# Main_Motor_Connector.net
KiCad netlist of a schematic drawn in Altium Designer
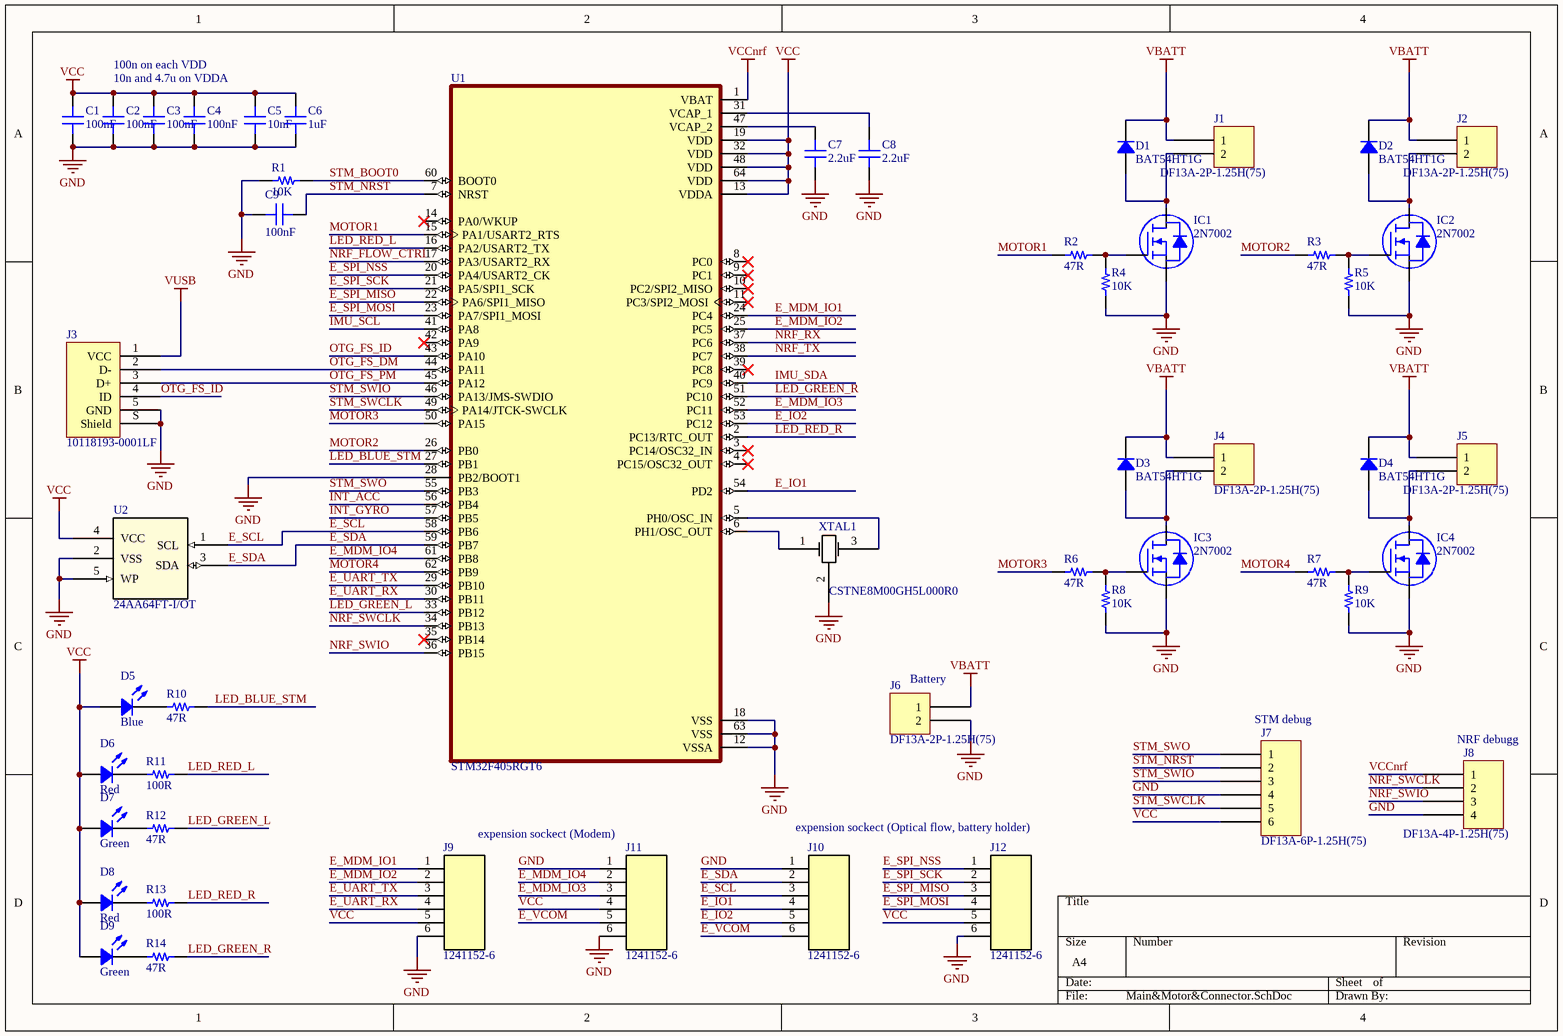
[diagram p0: Main&Motor&Connector.SchDoc]

(export (version "E")
  (design (tool "Eeschema 10.0.6"))
  (components
    (comp (ref "C1")
      (value "100nF")
      (footprint "CAP 0402_1005")
      (description "CAP CER 0.1UF 16V Y5V 0402")
      (fields (field (name "PART NUMBER") "C0402C104M4VACTU") (field (name "MANUFACTURER") "KEMET"))
      (libsource (lib "Celestial Altium Library - altium_library") (part "Capacitor"))
    )
    (comp (ref "C2")
      (value "100nF")
      (footprint "CAP 0402_1005")
      (description "CAP CER 0.1UF 16V Y5V 0402")
      (fields (field (name "PART NUMBER") "C0402C104M4VACTU") (field (name "MANUFACTURER") "KEMET"))
      (libsource (lib "Celestial Altium Library - altium_library") (part "Capacitor"))
    )
    (comp (ref "C3")
      (value "100nF")
      (footprint "CAP 0402_1005")
      (description "CAP CER 0.1UF 16V Y5V 0402")
      (fields (field (name "PART NUMBER") "C0402C104M4VACTU") (field (name "MANUFACTURER") "KEMET"))
      (libsource (lib "Celestial Altium Library - altium_library") (part "Capacitor"))
    )
    (comp (ref "C4")
      (value "100nF")
      (footprint "CAP 0402_1005")
      (description "CAP CER 0.1UF 16V Y5V 0402")
      (fields (field (name "PART NUMBER") "C0402C104M4VACTU") (field (name "MANUFACTURER") "KEMET"))
      (libsource (lib "Celestial Altium Library - altium_library") (part "Capacitor"))
    )
    (comp (ref "C5")
      (value "10nF")
      (footprint "CAP 0402_1005")
      (description "CAP CER 0.1UF 16V Y5V 0402")
      (fields (field (name "PART NUMBER") "C0402C104M4VACTU") (field (name "MANUFACTURER") "KEMET"))
      (libsource (lib "Celestial Altium Library - altium_library") (part "Capacitor"))
    )
    (comp (ref "C6")
      (value "1uF")
      (footprint "CAP 0402_1005")
      (description "CAP CER 0.1UF 16V Y5V 0402")
      (fields (field (name "PART NUMBER") "C0402C104M4VACTU") (field (name "MANUFACTURER") "KEMET"))
      (libsource (lib "Celestial Altium Library - altium_library") (part "Capacitor"))
    )
    (comp (ref "C7")
      (value "2.2uF")
      (footprint "CAP 0603_1608")
      (description "CAP CER 100PF 50V C0G/NP0 0603")
      (fields (field (name "PART NUMBER") "C0603X101F5GAC7867") (field (name "MANUFACTURER") "KEMET"))
      (libsource (lib "Celestial Altium Library - altium_library") (part "Capacitor"))
    )
    (comp (ref "C8")
      (value "2.2uF")
      (footprint "CAP 0603_1608")
      (description "CAP CER 100PF 50V C0G/NP0 0603")
      (fields (field (name "PART NUMBER") "C0603X101F5GAC7867") (field (name "MANUFACTURER") "KEMET"))
      (libsource (lib "Celestial Altium Library - altium_library") (part "Capacitor"))
    )
    (comp (ref "C9")
      (value "100nF")
      (footprint "CAP 0402_1005")
      (description "CAP CER 0.1UF 16V Y5V 0402")
      (fields (field (name "PART NUMBER") "C0402C104M4VACTU") (field (name "MANUFACTURER") "KEMET"))
      (libsource (lib "Celestial Altium Library - altium_library") (part "Capacitor"))
    )
    (comp (ref "D1")
      (value "BAT54HT1G")
      (footprint "SOD323")
      (description "DIODE SCHOTTKY 30V 200MA SOD323")
      (fields (field (name "MANUFACTURER") "ON Semiconductor"))
      (libsource (lib "Celestial Altium Library - altium_library") (part "Diode"))
    )
    (comp (ref "D2")
      (value "BAT54HT1G")
      (footprint "SOD323")
      (description "DIODE SCHOTTKY 30V 200MA SOD323")
      (fields (field (name "MANUFACTURER") "ON Semiconductor"))
      (libsource (lib "Celestial Altium Library - altium_library") (part "Diode"))
    )
    (comp (ref "D3")
      (value "BAT54HT1G")
      (footprint "SOD323")
      (description "DIODE SCHOTTKY 30V 200MA SOD323")
      (fields (field (name "MANUFACTURER") "ON Semiconductor"))
      (libsource (lib "Celestial Altium Library - altium_library") (part "Diode"))
    )
    (comp (ref "D4")
      (value "BAT54HT1G")
      (footprint "SOD323")
      (description "DIODE SCHOTTKY 30V 200MA SOD323")
      (fields (field (name "MANUFACTURER") "ON Semiconductor"))
      (libsource (lib "Celestial Altium Library - altium_library") (part "Diode"))
    )
    (comp (ref "D5")
      (value "Blue")
      (footprint "LED 0603_1608 BLUE")
      (description "LED BLUE CLEAR 2SMD")
      (fields (field (name "PART NUMBER") "XZFBB53W-1") (field (name "MANUFACTURER") "SunLED"))
      (libsource (lib "Celestial Altium Library - altium_library") (part "LED"))
    )
    (comp (ref "D6")
      (value "Red")
      (footprint "LED 0603_1608 RED")
      (description "LED RED 0603 SMD")
      (fields (field (name "PART NUMBER") "5973005507F") (field (name "MANUFACTURER") "Dialight"))
      (libsource (lib "Celestial Altium Library - altium_library") (part "LED"))
    )
    (comp (ref "D7")
      (value "Green")
      (footprint "LED 0603_1608 GREEN")
      (description "LED GREEN CLEAR CHIP SMD")
      (fields (field (name "PART NUMBER") "XZVG53W-3") (field (name "MANUFACTURER") "SunLED"))
      (libsource (lib "Celestial Altium Library - altium_library") (part "LED"))
    )
    (comp (ref "D8")
      (value "Red")
      (footprint "LED 0603_1608 RED")
      (description "LED RED 0603 SMD")
      (fields (field (name "PART NUMBER") "5973005507F") (field (name "MANUFACTURER") "Dialight"))
      (libsource (lib "Celestial Altium Library - altium_library") (part "LED"))
    )
    (comp (ref "D9")
      (value "Green")
      (footprint "LED 0603_1608 GREEN")
      (description "LED GREEN CLEAR CHIP SMD")
      (fields (field (name "PART NUMBER") "XZVG53W-3") (field (name "MANUFACTURER") "SunLED"))
      (libsource (lib "Celestial Altium Library - altium_library") (part "LED"))
    )
    (comp (ref "IC1")
      (value "2N7002")
      (footprint "ON SEMI SOT-23-3")
      (description "MOSFET N-CH 60V 115MA SOT-23")
      (fields (field (name "MANUFACTURER") "ON Semiconductor"))
      (libsource (lib "Celestial Altium Library - altium_library") (part "ON SEMI MOSFET N-CH SOT-23-3"))
    )
    (comp (ref "IC2")
      (value "2N7002")
      (footprint "ON SEMI SOT-23-3")
      (description "MOSFET N-CH 60V 115MA SOT-23")
      (fields (field (name "MANUFACTURER") "ON Semiconductor"))
      (libsource (lib "Celestial Altium Library - altium_library") (part "ON SEMI MOSFET N-CH SOT-23-3"))
    )
    (comp (ref "IC3")
      (value "2N7002")
      (footprint "ON SEMI SOT-23-3")
      (description "MOSFET N-CH 60V 115MA SOT-23")
      (fields (field (name "MANUFACTURER") "ON Semiconductor"))
      (libsource (lib "Celestial Altium Library - altium_library") (part "ON SEMI MOSFET N-CH SOT-23-3"))
    )
    (comp (ref "IC4")
      (value "2N7002")
      (footprint "ON SEMI SOT-23-3")
      (description "MOSFET N-CH 60V 115MA SOT-23")
      (fields (field (name "MANUFACTURER") "ON Semiconductor"))
      (libsource (lib "Celestial Altium Library - altium_library") (part "ON SEMI MOSFET N-CH SOT-23-3"))
    )
    (comp (ref "J1")
      (value "DF13A-2P-1.25H(75)")
      (footprint "HIROSE DF13A-2P-1.25H")
      (description "CONN HEADER SMD R/A 2POS 1.25MM")
      (fields (field (name "MANUFACTURER") "Hirose Electric Co Ltd"))
      (libsource (lib "Celestial Altium Library - altium_library") (part "2 Pin"))
    )
    (comp (ref "J2")
      (value "DF13A-2P-1.25H(75)")
      (footprint "HIROSE DF13A-2P-1.25H")
      (description "CONN HEADER SMD R/A 2POS 1.25MM")
      (fields (field (name "MANUFACTURER") "Hirose Electric Co Ltd"))
      (libsource (lib "Celestial Altium Library - altium_library") (part "2 Pin"))
    )
    (comp (ref "J3")
      (value "10118193-0001LF")
      (footprint "FCI USB 10118193-0001LF")
      (description "CONN RCPT USB2.0 MICRO B SMD R/A")
      (fields (field (name "MANUFACTURER") "Amphenol ICC (FCI)"))
      (libsource (lib "Celestial Altium Library - altium_library") (part "USB 2.0 Type B Micro"))
    )
    (comp (ref "J4")
      (value "DF13A-2P-1.25H(75)")
      (footprint "HIROSE DF13A-2P-1.25H")
      (description "CONN HEADER SMD R/A 2POS 1.25MM")
      (fields (field (name "MANUFACTURER") "Hirose Electric Co Ltd"))
      (libsource (lib "Celestial Altium Library - altium_library") (part "2 Pin"))
    )
    (comp (ref "J5")
      (value "DF13A-2P-1.25H(75)")
      (footprint "HIROSE DF13A-2P-1.25H")
      (description "CONN HEADER SMD R/A 2POS 1.25MM")
      (fields (field (name "MANUFACTURER") "Hirose Electric Co Ltd"))
      (libsource (lib "Celestial Altium Library - altium_library") (part "2 Pin"))
    )
    (comp (ref "J6")
      (value "DF13A-2P-1.25H(75)")
      (footprint "HIROSE DF13A-2P-1.25H")
      (description "CONN HEADER SMD R/A 2POS 1.25MM")
      (fields (field (name "MANUFACTURER") "Hirose Electric Co Ltd"))
      (libsource (lib "") (part "2 Pin_1"))
    )
    (comp (ref "J7")
      (value "DF13A-6P-1.25H(75)")
      (footprint "HIROSE DF13A-6P-1.25H")
      (description "CONN HEADER SMD R/A 6POS 1.25MM")
      (fields (field (name "MANUFACTURER") "Hirose Electric Co Ltd"))
      (libsource (lib "Celestial Altium Library - altium_library") (part "6 Pin"))
    )
    (comp (ref "J8")
      (value "DF13A-4P-1.25H(75)")
      (footprint "HIROSE DF13A-4P-1.25H")
      (description "CONN HEADER SMD R/A 4POS 1.25MM")
      (fields (field (name "MANUFACTURER") "Hirose Electric Co Ltd"))
      (libsource (lib "Celestial Altium Library - altium_library") (part "4 Pin"))
    )
    (comp (ref "J9")
      (value "1241152-6")
      (footprint "CONN_1241152-6_T")
      (description "con 6pos 2.54mm TE connectivity")
      (fields (field (name "COPYRIGHT") "Copyright (C) 2016 Accelerated Designs. All rights reserved"))
      (libsource (lib "Schlib1") (part "1241152-6"))
    )
    (comp (ref "J10")
      (value "1241152-6")
      (footprint "CONN_1241152-6_T")
      (description "con 6pos 2.54mm TE connectivity")
      (fields (field (name "COPYRIGHT") "Copyright (C) 2016 Accelerated Designs. All rights reserved"))
      (libsource (lib "Schlib1") (part "1241152-6"))
    )
    (comp (ref "J11")
      (value "1241152-6")
      (footprint "CONN_1241152-6_T")
      (description "con 6pos 2.54mm TE connectivity")
      (fields (field (name "COPYRIGHT") "Copyright (C) 2016 Accelerated Designs. All rights reserved"))
      (libsource (lib "Schlib1") (part "1241152-6"))
    )
    (comp (ref "J12")
      (value "1241152-6")
      (footprint "CONN_1241152-6_T")
      (description "con 6pos 2.54mm TE connectivity")
      (fields (field (name "COPYRIGHT") "Copyright (C) 2016 Accelerated Designs. All rights reserved"))
      (libsource (lib "Schlib1") (part "1241152-6"))
    )
    (comp (ref "R1")
      (value "10K")
      (footprint "RES 0402_1005")
      (description "RES SMD 4.7K OHM 1% 1/16W 0402")
      (fields (field (name "PART NUMBER") "RT0402FRE074K7L") (field (name "MANUFACTURER") "Yageo"))
      (libsource (lib "Celestial Altium Library - altium_library") (part "Resistor"))
    )
    (comp (ref "R2")
      (value "47R")
      (footprint "RES 0603_1608")
      (description "RES SMD 10K OHM 1% 1/10W 0603")
      (fields (field (name "PART NUMBER") "AC0603FR-0710KL") (field (name "MANUFACTURER") "Yageo"))
      (libsource (lib "Celestial Altium Library - altium_library") (part "Resistor"))
    )
    (comp (ref "R3")
      (value "47R")
      (footprint "RES 0603_1608")
      (description "RES SMD 10K OHM 1% 1/10W 0603")
      (fields (field (name "PART NUMBER") "AC0603FR-0710KL") (field (name "MANUFACTURER") "Yageo"))
      (libsource (lib "Celestial Altium Library - altium_library") (part "Resistor"))
    )
    (comp (ref "R4")
      (value "10K")
      (footprint "RES 0603_1608")
      (description "RES SMD 10K OHM 1% 1/10W 0603")
      (fields (field (name "PART NUMBER") "AC0603FR-0710KL") (field (name "MANUFACTURER") "Yageo"))
      (libsource (lib "Celestial Altium Library - altium_library") (part "Resistor"))
    )
    (comp (ref "R5")
      (value "10K")
      (footprint "RES 0603_1608")
      (description "RES SMD 10K OHM 1% 1/10W 0603")
      (fields (field (name "PART NUMBER") "AC0603FR-0710KL") (field (name "MANUFACTURER") "Yageo"))
      (libsource (lib "Celestial Altium Library - altium_library") (part "Resistor"))
    )
    (comp (ref "R6")
      (value "47R")
      (footprint "RES 0603_1608")
      (description "RES SMD 10K OHM 1% 1/10W 0603")
      (fields (field (name "PART NUMBER") "AC0603FR-0710KL") (field (name "MANUFACTURER") "Yageo"))
      (libsource (lib "Celestial Altium Library - altium_library") (part "Resistor"))
    )
    (comp (ref "R7")
      (value "47R")
      (footprint "RES 0603_1608")
      (description "RES SMD 10K OHM 1% 1/10W 0603")
      (fields (field (name "PART NUMBER") "AC0603FR-0710KL") (field (name "MANUFACTURER") "Yageo"))
      (libsource (lib "Celestial Altium Library - altium_library") (part "Resistor"))
    )
    (comp (ref "R8")
      (value "10K")
      (footprint "RES 0603_1608")
      (description "RES SMD 10K OHM 1% 1/10W 0603")
      (fields (field (name "PART NUMBER") "AC0603FR-0710KL") (field (name "MANUFACTURER") "Yageo"))
      (libsource (lib "Celestial Altium Library - altium_library") (part "Resistor"))
    )
    (comp (ref "R9")
      (value "10K")
      (footprint "RES 0603_1608")
      (description "RES SMD 10K OHM 1% 1/10W 0603")
      (fields (field (name "PART NUMBER") "AC0603FR-0710KL") (field (name "MANUFACTURER") "Yageo"))
      (libsource (lib "Celestial Altium Library - altium_library") (part "Resistor"))
    )
    (comp (ref "R10")
      (value "47R")
      (footprint "RES 0603_1608")
      (description "RES SMD 10K OHM 1% 1/10W 0603")
      (fields (field (name "PART NUMBER") "AC0603FR-0710KL") (field (name "MANUFACTURER") "Yageo"))
      (libsource (lib "Celestial Altium Library - altium_library") (part "Resistor"))
    )
    (comp (ref "R11")
      (value "100R")
      (footprint "RES 0603_1608")
      (description "RES SMD 10K OHM 1% 1/10W 0603")
      (fields (field (name "PART NUMBER") "AC0603FR-0710KL") (field (name "MANUFACTURER") "Yageo"))
      (libsource (lib "Celestial Altium Library - altium_library") (part "Resistor"))
    )
    (comp (ref "R12")
      (value "47R")
      (footprint "RES 0603_1608")
      (description "RES SMD 10K OHM 1% 1/10W 0603")
      (fields (field (name "PART NUMBER") "AC0603FR-0710KL") (field (name "MANUFACTURER") "Yageo"))
      (libsource (lib "Celestial Altium Library - altium_library") (part "Resistor"))
    )
    (comp (ref "R13")
      (value "100R")
      (footprint "RES 0603_1608")
      (description "RES SMD 10K OHM 1% 1/10W 0603")
      (fields (field (name "PART NUMBER") "AC0603FR-0710KL") (field (name "MANUFACTURER") "Yageo"))
      (libsource (lib "Celestial Altium Library - altium_library") (part "Resistor"))
    )
    (comp (ref "R14")
      (value "47R")
      (footprint "RES 0603_1608")
      (description "RES SMD 10K OHM 1% 1/10W 0603")
      (fields (field (name "PART NUMBER") "AC0603FR-0710KL") (field (name "MANUFACTURER") "Yageo"))
      (libsource (lib "Celestial Altium Library - altium_library") (part "Resistor"))
    )
    (comp (ref "U1")
      (value "STM32F405RGT6")
      (footprint "QFP50P1200X1200X160-64N")
      (description "ARMÂ® CortexÂ®-M4 STM32F4 Microcontroller IC 32-Bit 168MHz 1MB _1M x 8_ FLASH 64-LQFP _10x10_")
      (fields (field (name "MF") "STMicroelectronics") (field (name "DIGI-KEY_PART_NUMBER") "497-11767-ND"))
      (libsource (lib "altium-import") (part "root_0_STM32F405RGT6_"))
    )
    (comp (ref "U2")
      (value "24AA64FT-I/OT")
      (footprint "SOT-23-5_MC_MCH")
      (description "No Description Available")
      (fields (field (name "COPYRIGHT") "Copyright (C) 2018 Accelerated Designs. All rights reserved"))
      (libsource (lib "Schlib1") (part "24AA64FT-I/OT"))
    )
    (comp (ref "XTAL1")
      (value "CSTNE8M00GH5L000R0")
      (footprint "CSTNE8M00GH5L000")
      (description "No Description Available")
      (fields (field (name "COPYRIGHT") "Copyright (C) 2018 Accelerated Designs. All rights reserved"))
      (libsource (lib "Schlib1") (part "CSTNE8M00GH5L000"))
    )
  )
  (nets
    (net (code "1") (name "/E_IO1") (class "Default")
      (node (ref "J10") (pin "4") (pinfunction "4_4") (pintype "passive"))
      (node (ref "U1") (pin "54") (pinfunction "PD2_54") (pintype "bidirectional"))
    )
    (net (code "2") (name "/E_IO2") (class "Default")
      (node (ref "J10") (pin "5") (pinfunction "5_5") (pintype "passive"))
      (node (ref "U1") (pin "53") (pinfunction "PC12_53") (pintype "bidirectional"))
    )
    (net (code "3") (name "/E_MDM_IO1") (class "Default")
      (node (ref "J9") (pin "1") (pinfunction "1_1") (pintype "passive"))
      (node (ref "U1") (pin "24") (pinfunction "PC4_24") (pintype "bidirectional"))
    )
    (net (code "4") (name "/E_MDM_IO2") (class "Default")
      (node (ref "J9") (pin "2") (pinfunction "2_2") (pintype "passive"))
      (node (ref "U1") (pin "25") (pinfunction "PC5_25") (pintype "bidirectional"))
    )
    (net (code "5") (name "/E_MDM_IO3") (class "Default")
      (node (ref "J11") (pin "3") (pinfunction "3_3") (pintype "passive"))
      (node (ref "U1") (pin "52") (pinfunction "PC11_52") (pintype "bidirectional"))
    )
    (net (code "6") (name "/E_MDM_IO4") (class "Default")
      (node (ref "J11") (pin "2") (pinfunction "2_2") (pintype "passive"))
      (node (ref "U1") (pin "61") (pinfunction "PB8_61") (pintype "bidirectional"))
    )
    (net (code "7") (name "/E_SCL") (class "Default")
      (node (ref "J10") (pin "3") (pinfunction "3_3") (pintype "passive"))
      (node (ref "U1") (pin "58") (pinfunction "PB6_58") (pintype "bidirectional"))
      (node (ref "U2") (pin "1") (pinfunction "SCL_1") (pintype "input"))
    )
    (net (code "8") (name "/E_SDA") (class "Default")
      (node (ref "J10") (pin "2") (pinfunction "2_2") (pintype "passive"))
      (node (ref "U1") (pin "59") (pinfunction "PB7_59") (pintype "bidirectional"))
      (node (ref "U2") (pin "3") (pinfunction "SDA_3") (pintype "bidirectional"))
    )
    (net (code "9") (name "/E_SPI_MISO") (class "Default")
      (node (ref "J12") (pin "3") (pinfunction "3_3") (pintype "passive"))
      (node (ref "U1") (pin "22") (pinfunction "PA6/SPI1_MISO_22") (pintype "bidirectional"))
    )
    (net (code "10") (name "/E_SPI_MOSI") (class "Default")
      (node (ref "J12") (pin "4") (pinfunction "4_4") (pintype "passive"))
      (node (ref "U1") (pin "23") (pinfunction "PA7/SPI1_MOSI_23") (pintype "bidirectional"))
    )
    (net (code "11") (name "/E_SPI_NSS") (class "Default")
      (node (ref "J12") (pin "1") (pinfunction "1_1") (pintype "passive"))
      (node (ref "U1") (pin "20") (pinfunction "PA4/USART2_CK_20") (pintype "bidirectional"))
    )
    (net (code "12") (name "/E_SPI_SCK") (class "Default")
      (node (ref "J12") (pin "2") (pinfunction "2_2") (pintype "passive"))
      (node (ref "U1") (pin "21") (pinfunction "PA5/SPI1_SCK_21") (pintype "bidirectional"))
    )
    (net (code "13") (name "/E_UART_RX") (class "Default")
      (node (ref "J9") (pin "4") (pinfunction "4_4") (pintype "passive"))
      (node (ref "U1") (pin "30") (pinfunction "PB11_30") (pintype "bidirectional"))
    )
    (net (code "14") (name "/E_UART_TX") (class "Default")
      (node (ref "J9") (pin "3") (pinfunction "3_3") (pintype "passive"))
      (node (ref "U1") (pin "29") (pinfunction "PB10_29") (pintype "bidirectional"))
    )
    (net (code "15") (name "/E_VCOM") (class "Default")
      (node (ref "J10") (pin "6") (pinfunction "6_6") (pintype "passive"))
      (node (ref "J11") (pin "5") (pinfunction "5_5") (pintype "passive"))
    )
    (net (code "16") (name "/IMU_SCL") (class "Default")
      (node (ref "U1") (pin "41") (pinfunction "PA8_41") (pintype "bidirectional"))
    )
    (net (code "17") (name "/IMU_SDA") (class "Default")
      (node (ref "U1") (pin "40") (pinfunction "PC9_40") (pintype "bidirectional"))
    )
    (net (code "18") (name "/INT_ACC") (class "Default")
      (node (ref "U1") (pin "56") (pinfunction "PB4_56") (pintype "bidirectional"))
    )
    (net (code "19") (name "/INT_GYRO") (class "Default")
      (node (ref "U1") (pin "57") (pinfunction "PB5_57") (pintype "bidirectional"))
    )
    (net (code "20") (name "/LED_BLUE_STM") (class "Default")
      (node (ref "R10") (pin "1") (pinfunction "1_1") (pintype "passive"))
      (node (ref "U1") (pin "27") (pinfunction "PB1_27") (pintype "bidirectional"))
    )
    (net (code "21") (name "/LED_GREEN_L") (class "Default")
      (node (ref "R12") (pin "1") (pinfunction "1_1") (pintype "passive"))
      (node (ref "U1") (pin "33") (pinfunction "PB12_33") (pintype "bidirectional"))
    )
    (net (code "22") (name "/LED_GREEN_R") (class "Default")
      (node (ref "R14") (pin "1") (pinfunction "1_1") (pintype "passive"))
      (node (ref "U1") (pin "51") (pinfunction "PC10_51") (pintype "bidirectional"))
    )
    (net (code "23") (name "/LED_RED_L") (class "Default")
      (node (ref "R11") (pin "1") (pinfunction "1_1") (pintype "passive"))
      (node (ref "U1") (pin "16") (pinfunction "PA2/USART2_TX_16") (pintype "bidirectional"))
    )
    (net (code "24") (name "/LED_RED_R") (class "Default")
      (node (ref "R13") (pin "1") (pinfunction "1_1") (pintype "passive"))
      (node (ref "U1") (pin "2") (pinfunction "PC13/RTC_OUT_2") (pintype "bidirectional"))
    )
    (net (code "25") (name "/MOTOR1") (class "Default")
      (node (ref "R2") (pin "1") (pinfunction "1_1") (pintype "passive"))
      (node (ref "U1") (pin "15") (pinfunction "PA1/USART2_RTS_15") (pintype "bidirectional"))
    )
    (net (code "26") (name "/MOTOR2") (class "Default")
      (node (ref "R3") (pin "1") (pinfunction "1_1") (pintype "passive"))
      (node (ref "U1") (pin "26") (pinfunction "PB0_26") (pintype "bidirectional"))
    )
    (net (code "27") (name "/MOTOR3") (class "Default")
      (node (ref "R6") (pin "1") (pinfunction "1_1") (pintype "passive"))
      (node (ref "U1") (pin "50") (pinfunction "PA15_50") (pintype "bidirectional"))
    )
    (net (code "28") (name "/MOTOR4") (class "Default")
      (node (ref "R7") (pin "1") (pinfunction "1_1") (pintype "passive"))
      (node (ref "U1") (pin "62") (pinfunction "PB9_62") (pintype "bidirectional"))
    )
    (net (code "29") (name "/NRF_FLOW_CTRL") (class "Default")
      (node (ref "U1") (pin "17") (pinfunction "PA3/USART2_RX_17") (pintype "bidirectional"))
    )
    (net (code "30") (name "/NRF_RX") (class "Default")
      (node (ref "U1") (pin "37") (pinfunction "PC6_37") (pintype "bidirectional"))
    )
    (net (code "31") (name "/NRF_SWCLK") (class "Default")
      (node (ref "J8") (pin "2") (pinfunction "2_2") (pintype "passive"))
      (node (ref "U1") (pin "34") (pinfunction "PB13_34") (pintype "bidirectional"))
    )
    (net (code "32") (name "/NRF_SWIO") (class "Default")
      (node (ref "J8") (pin "3") (pinfunction "3_3") (pintype "passive"))
      (node (ref "U1") (pin "36") (pinfunction "PB15_36") (pintype "bidirectional"))
    )
    (net (code "33") (name "/NRF_TX") (class "Default")
      (node (ref "U1") (pin "38") (pinfunction "PC7_38") (pintype "bidirectional"))
    )
    (net (code "34") (name "/OTG_FS_DM") (class "Default")
      (node (ref "J3") (pin "2") (pinfunction "D-_2") (pintype "passive"))
      (node (ref "U1") (pin "44") (pinfunction "PA11_44") (pintype "bidirectional"))
    )
    (net (code "35") (name "/OTG_FS_ID") (class "Default")
      (node (ref "J3") (pin "4") (pinfunction "ID_4") (pintype "passive"))
      (node (ref "U1") (pin "43") (pinfunction "PA10_43") (pintype "bidirectional"))
    )
    (net (code "36") (name "/OTG_FS_PM") (class "Default")
      (node (ref "J3") (pin "3") (pinfunction "D+_3") (pintype "passive"))
      (node (ref "U1") (pin "45") (pinfunction "PA12_45") (pintype "bidirectional"))
    )
    (net (code "37") (name "/STM_BOOT0") (class "Default")
      (node (ref "R1") (pin "2") (pinfunction "2_2") (pintype "passive"))
      (node (ref "U1") (pin "60") (pinfunction "BOOT0_60") (pintype "bidirectional"))
    )
    (net (code "38") (name "/STM_NRST") (class "Default")
      (node (ref "C9") (pin "1") (pinfunction "1_1") (pintype "passive"))
      (node (ref "J7") (pin "2") (pinfunction "2_2") (pintype "passive"))
      (node (ref "U1") (pin "7") (pinfunction "NRST_7") (pintype "bidirectional"))
    )
    (net (code "39") (name "/STM_SWCLK") (class "Default")
      (node (ref "J7") (pin "5") (pinfunction "5_5") (pintype "passive"))
      (node (ref "U1") (pin "49") (pinfunction "PA14/JTCK-SWCLK_49") (pintype "bidirectional"))
    )
    (net (code "40") (name "/STM_SWIO") (class "Default")
      (node (ref "J7") (pin "3") (pinfunction "3_3") (pintype "passive"))
      (node (ref "U1") (pin "46") (pinfunction "PA13/JMS-SWDIO_46") (pintype "bidirectional"))
    )
    (net (code "41") (name "/STM_SWO") (class "Default")
      (node (ref "J7") (pin "1") (pinfunction "1_1") (pintype "passive"))
      (node (ref "U1") (pin "55") (pinfunction "PB3_55") (pintype "bidirectional"))
    )
    (net (code "42") (name "GND") (class "Default")
      (node (ref "C1") (pin "1") (pinfunction "1_1") (pintype "passive"))
      (node (ref "C2") (pin "1") (pinfunction "1_1") (pintype "passive"))
      (node (ref "C3") (pin "1") (pinfunction "1_1") (pintype "passive"))
      (node (ref "C4") (pin "1") (pinfunction "1_1") (pintype "passive"))
      (node (ref "C5") (pin "1") (pinfunction "1_1") (pintype "passive"))
      (node (ref "C6") (pin "1") (pinfunction "1_1") (pintype "passive"))
      (node (ref "C7") (pin "2") (pinfunction "2_2") (pintype "passive"))
      (node (ref "C8") (pin "1") (pinfunction "1_1") (pintype "passive"))
      (node (ref "C9") (pin "2") (pinfunction "2_2") (pintype "passive"))
      (node (ref "IC1") (pin "2") (pinfunction "S_2") (pintype "passive"))
      (node (ref "IC2") (pin "2") (pinfunction "S_2") (pintype "passive"))
      (node (ref "IC3") (pin "2") (pinfunction "S_2") (pintype "passive"))
      (node (ref "IC4") (pin "2") (pinfunction "S_2") (pintype "passive"))
      (node (ref "J10") (pin "1") (pinfunction "1_1") (pintype "passive"))
      (node (ref "J11") (pin "1") (pinfunction "1_1") (pintype "passive"))
      (node (ref "J11") (pin "6") (pinfunction "6_6") (pintype "passive"))
      (node (ref "J12") (pin "6") (pinfunction "6_6") (pintype "passive"))
      (node (ref "J3") (pin "5") (pinfunction "GND_5") (pintype "passive"))
      (node (ref "J3") (pin "S") (pinfunction "Shield_S") (pintype "passive"))
      (node (ref "J6") (pin "2") (pinfunction "2_2") (pintype "passive"))
      (node (ref "J7") (pin "4") (pinfunction "4_4") (pintype "passive"))
      (node (ref "J8") (pin "4") (pinfunction "4_4") (pintype "passive"))
      (node (ref "J9") (pin "6") (pinfunction "6_6") (pintype "passive"))
      (node (ref "R1") (pin "1") (pinfunction "1_1") (pintype "passive"))
      (node (ref "R4") (pin "1") (pinfunction "1_1") (pintype "passive"))
      (node (ref "R5") (pin "1") (pinfunction "1_1") (pintype "passive"))
      (node (ref "R8") (pin "1") (pinfunction "1_1") (pintype "passive"))
      (node (ref "R9") (pin "1") (pinfunction "1_1") (pintype "passive"))
      (node (ref "U1") (pin "12") (pinfunction "VSSA_12") (pintype "power_in"))
      (node (ref "U1") (pin "18") (pinfunction "VSS_18") (pintype "power_in"))
      (node (ref "U1") (pin "28") (pinfunction "PB2/BOOT1_28") (pintype "passive"))
      (node (ref "U1") (pin "63") (pinfunction "VSS_63") (pintype "power_in"))
      (node (ref "U2") (pin "2") (pinfunction "VSS_2") (pintype "passive"))
      (node (ref "U2") (pin "5") (pinfunction "WP_5") (pintype "input"))
      (node (ref "XTAL1") (pin "2") (pinfunction "GND_2") (pintype "passive"))
    )
    (net (code "43") (name "Net-(D5-Pad2)") (class "Default")
      (node (ref "D5") (pin "2") (pinfunction "2_2") (pintype "passive"))
      (node (ref "R10") (pin "2") (pinfunction "2_2") (pintype "passive"))
    )
    (net (code "44") (name "Net-(D6-Pad2)") (class "Default")
      (node (ref "D6") (pin "2") (pinfunction "2_2") (pintype "passive"))
      (node (ref "R11") (pin "2") (pinfunction "2_2") (pintype "passive"))
    )
    (net (code "45") (name "Net-(D7-Pad2)") (class "Default")
      (node (ref "D7") (pin "2") (pinfunction "2_2") (pintype "passive"))
      (node (ref "R12") (pin "2") (pinfunction "2_2") (pintype "passive"))
    )
    (net (code "46") (name "Net-(D8-Pad2)") (class "Default")
      (node (ref "D8") (pin "2") (pinfunction "2_2") (pintype "passive"))
      (node (ref "R13") (pin "2") (pinfunction "2_2") (pintype "passive"))
    )
    (net (code "47") (name "Net-(D9-Pad2)") (class "Default")
      (node (ref "D9") (pin "2") (pinfunction "2_2") (pintype "passive"))
      (node (ref "R14") (pin "2") (pinfunction "2_2") (pintype "passive"))
    )
    (net (code "48") (name "Net-(IC1-D)") (class "Default")
      (node (ref "D1") (pin "1") (pinfunction "1_1") (pintype "passive"))
      (node (ref "IC1") (pin "3") (pinfunction "D_3") (pintype "passive"))
      (node (ref "J1") (pin "2") (pinfunction "2_2") (pintype "passive"))
    )
    (net (code "49") (name "Net-(IC1-G)") (class "Default")
      (node (ref "IC1") (pin "1") (pinfunction "G_1") (pintype "passive"))
      (node (ref "R2") (pin "2") (pinfunction "2_2") (pintype "passive"))
      (node (ref "R4") (pin "2") (pinfunction "2_2") (pintype "passive"))
    )
    (net (code "50") (name "Net-(IC2-D)") (class "Default")
      (node (ref "D2") (pin "1") (pinfunction "1_1") (pintype "passive"))
      (node (ref "IC2") (pin "3") (pinfunction "D_3") (pintype "passive"))
      (node (ref "J2") (pin "2") (pinfunction "2_2") (pintype "passive"))
    )
    (net (code "51") (name "Net-(IC2-G)") (class "Default")
      (node (ref "IC2") (pin "1") (pinfunction "G_1") (pintype "passive"))
      (node (ref "R3") (pin "2") (pinfunction "2_2") (pintype "passive"))
      (node (ref "R5") (pin "2") (pinfunction "2_2") (pintype "passive"))
    )
    (net (code "52") (name "Net-(IC3-D)") (class "Default")
      (node (ref "D3") (pin "1") (pinfunction "1_1") (pintype "passive"))
      (node (ref "IC3") (pin "3") (pinfunction "D_3") (pintype "passive"))
      (node (ref "J4") (pin "2") (pinfunction "2_2") (pintype "passive"))
    )
    (net (code "53") (name "Net-(IC3-G)") (class "Default")
      (node (ref "IC3") (pin "1") (pinfunction "G_1") (pintype "passive"))
      (node (ref "R6") (pin "2") (pinfunction "2_2") (pintype "passive"))
      (node (ref "R8") (pin "2") (pinfunction "2_2") (pintype "passive"))
    )
    (net (code "54") (name "Net-(IC4-D)") (class "Default")
      (node (ref "D4") (pin "1") (pinfunction "1_1") (pintype "passive"))
      (node (ref "IC4") (pin "3") (pinfunction "D_3") (pintype "passive"))
      (node (ref "J5") (pin "2") (pinfunction "2_2") (pintype "passive"))
    )
    (net (code "55") (name "Net-(IC4-G)") (class "Default")
      (node (ref "IC4") (pin "1") (pinfunction "G_1") (pintype "passive"))
      (node (ref "R7") (pin "2") (pinfunction "2_2") (pintype "passive"))
      (node (ref "R9") (pin "2") (pinfunction "2_2") (pintype "passive"))
    )
    (net (code "56") (name "Net-(U1-PH0{slash}OSC_IN)") (class "Default")
      (node (ref "U1") (pin "5") (pinfunction "PH0/OSC_IN_5") (pintype "bidirectional"))
      (node (ref "XTAL1") (pin "3") (pinfunction "OUTPUT_3") (pintype "passive"))
    )
    (net (code "57") (name "Net-(U1-PH1{slash}OSC_OUT)") (class "Default")
      (node (ref "U1") (pin "6") (pinfunction "PH1/OSC_OUT_6") (pintype "bidirectional"))
      (node (ref "XTAL1") (pin "1") (pinfunction "INPUT_1") (pintype "passive"))
    )
    (net (code "58") (name "Net-(U1-VCAP_1)") (class "Default")
      (node (ref "C8") (pin "2") (pinfunction "2_2") (pintype "passive"))
      (node (ref "U1") (pin "31") (pinfunction "VCAP_1_31") (pintype "power_in"))
    )
    (net (code "59") (name "Net-(U1-VCAP_2)") (class "Default")
      (node (ref "C7") (pin "1") (pinfunction "1_1") (pintype "passive"))
      (node (ref "U1") (pin "47") (pinfunction "VCAP_2_47") (pintype "power_in"))
    )
    (net (code "60") (name "VBATT") (class "Default")
      (node (ref "D1") (pin "2") (pinfunction "2_2") (pintype "passive"))
      (node (ref "D2") (pin "2") (pinfunction "2_2") (pintype "passive"))
      (node (ref "D3") (pin "2") (pinfunction "2_2") (pintype "passive"))
      (node (ref "D4") (pin "2") (pinfunction "2_2") (pintype "passive"))
      (node (ref "J1") (pin "1") (pinfunction "1_1") (pintype "passive"))
      (node (ref "J2") (pin "1") (pinfunction "1_1") (pintype "passive"))
      (node (ref "J4") (pin "1") (pinfunction "1_1") (pintype "passive"))
      (node (ref "J5") (pin "1") (pinfunction "1_1") (pintype "passive"))
      (node (ref "J6") (pin "1") (pinfunction "1_1") (pintype "passive"))
    )
    (net (code "61") (name "VCC") (class "Default")
      (node (ref "C1") (pin "2") (pinfunction "2_2") (pintype "passive"))
      (node (ref "C2") (pin "2") (pinfunction "2_2") (pintype "passive"))
      (node (ref "C3") (pin "2") (pinfunction "2_2") (pintype "passive"))
      (node (ref "C4") (pin "2") (pinfunction "2_2") (pintype "passive"))
      (node (ref "C5") (pin "2") (pinfunction "2_2") (pintype "passive"))
      (node (ref "C6") (pin "2") (pinfunction "2_2") (pintype "passive"))
      (node (ref "D5") (pin "1") (pinfunction "1_1") (pintype "passive"))
      (node (ref "D6") (pin "1") (pinfunction "1_1") (pintype "passive"))
      (node (ref "D7") (pin "1") (pinfunction "1_1") (pintype "passive"))
      (node (ref "D8") (pin "1") (pinfunction "1_1") (pintype "passive"))
      (node (ref "D9") (pin "1") (pinfunction "1_1") (pintype "passive"))
      (node (ref "J11") (pin "4") (pinfunction "4_4") (pintype "passive"))
      (node (ref "J12") (pin "5") (pinfunction "5_5") (pintype "passive"))
      (node (ref "J7") (pin "6") (pinfunction "6_6") (pintype "passive"))
      (node (ref "J9") (pin "5") (pinfunction "5_5") (pintype "passive"))
      (node (ref "U1") (pin "13") (pinfunction "VDDA_13") (pintype "power_in"))
      (node (ref "U1") (pin "19") (pinfunction "VDD_19") (pintype "power_in"))
      (node (ref "U1") (pin "32") (pinfunction "VDD_32") (pintype "power_in"))
      (node (ref "U1") (pin "48") (pinfunction "VDD_48") (pintype "power_in"))
      (node (ref "U1") (pin "64") (pinfunction "VDD_64") (pintype "power_in"))
      (node (ref "U2") (pin "4") (pinfunction "VCC_4") (pintype "power_in"))
    )
    (net (code "62") (name "VCCnrf") (class "Default")
      (node (ref "J8") (pin "1") (pinfunction "1_1") (pintype "passive"))
      (node (ref "U1") (pin "1") (pinfunction "VBAT_1") (pintype "power_in"))
    )
    (net (code "63") (name "VUSB") (class "Default")
      (node (ref "J3") (pin "1") (pinfunction "VCC_1") (pintype "passive"))
    )
    (net (code "64") (name "unconnected-(U1-PA0{slash}WKUP-Pad14)") (class "Default")
      (node (ref "U1") (pin "14") (pinfunction "PA0/WKUP_14") (pintype "bidirectional+no_connect"))
    )
    (net (code "65") (name "unconnected-(U1-PA9-Pad42)") (class "Default")
      (node (ref "U1") (pin "42") (pinfunction "PA9_42") (pintype "bidirectional+no_connect"))
    )
    (net (code "66") (name "unconnected-(U1-PB14-Pad35)") (class "Default")
      (node (ref "U1") (pin "35") (pinfunction "PB14_35") (pintype "bidirectional+no_connect"))
    )
    (net (code "67") (name "unconnected-(U1-PC0-Pad8)") (class "Default")
      (node (ref "U1") (pin "8") (pinfunction "PC0_8") (pintype "bidirectional+no_connect"))
    )
    (net (code "68") (name "unconnected-(U1-PC1-Pad9)") (class "Default")
      (node (ref "U1") (pin "9") (pinfunction "PC1_9") (pintype "bidirectional+no_connect"))
    )
    (net (code "69") (name "unconnected-(U1-PC2{slash}SPI2_MISO-Pad10)") (class "Default")
      (node (ref "U1") (pin "10") (pinfunction "PC2/SPI2_MISO_10") (pintype "bidirectional+no_connect"))
    )
    (net (code "70") (name "unconnected-(U1-PC3{slash}SPI2_MOSI-Pad11)") (class "Default")
      (node (ref "U1") (pin "11") (pinfunction "PC3/SPI2_MOSI_11") (pintype "bidirectional+no_connect"))
    )
    (net (code "71") (name "unconnected-(U1-PC8-Pad39)") (class "Default")
      (node (ref "U1") (pin "39") (pinfunction "PC8_39") (pintype "bidirectional+no_connect"))
    )
    (net (code "72") (name "unconnected-(U1-PC14{slash}OSC32_IN-Pad3)") (class "Default")
      (node (ref "U1") (pin "3") (pinfunction "PC14/OSC32_IN_3") (pintype "bidirectional+no_connect"))
    )
    (net (code "73") (name "unconnected-(U1-PC15{slash}OSC32_OUT-Pad4)") (class "Default")
      (node (ref "U1") (pin "4") (pinfunction "PC15/OSC32_OUT_4") (pintype "bidirectional+no_connect"))
    )
  )
)
